# Schematic.net
KiCad netlist of a schematic drawn in Altium Designer
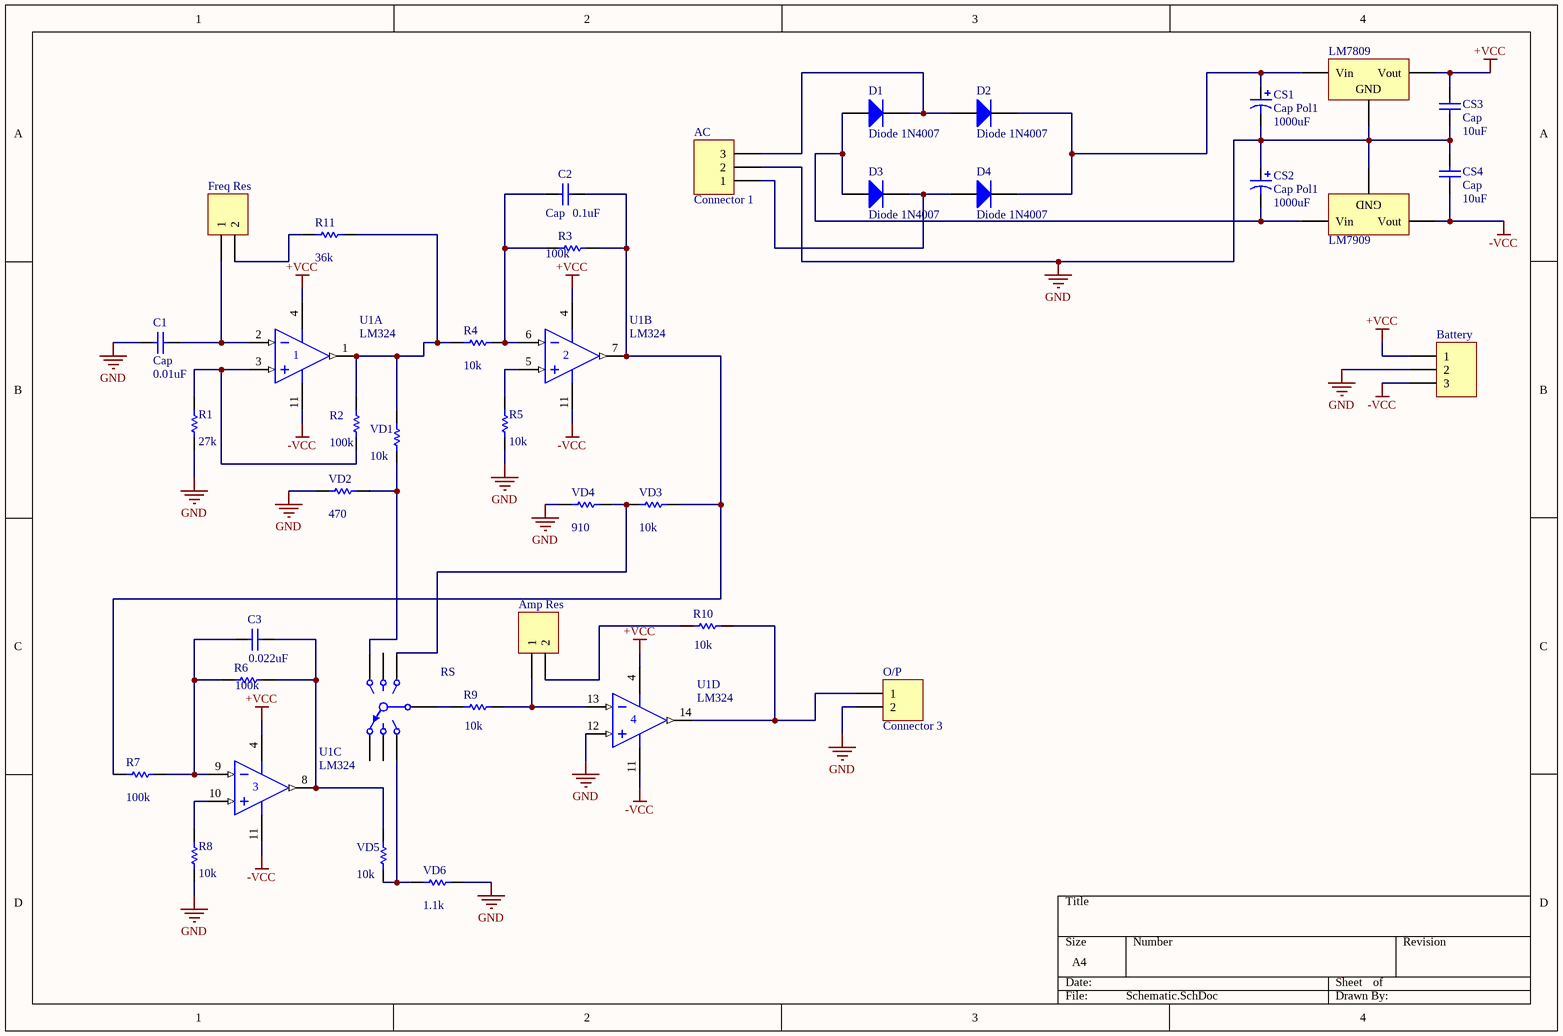
[diagram p0: Schematic.SchDoc]

(export (version "E")
  (design (tool "Eeschema 10.0.6"))
  (components
    (comp (ref "AC")
      (value "Connector 1")
      (footprint "HDR1X3H")
      (description "Header, 3-Pin, Right Angle")
      (fields (field (name "PUBLISHER") "Altium Limited"))
      (libsource (lib "") (part "Header 3H_1"))
    )
    (comp (ref "Amp Res")
      (value "~")
      (footprint "HDR1X2")
      (description "Header, 2-Pin")
      (fields (field (name "PUBLISHER") "Altium Limited"))
      (libsource (lib "Miscellaneous Connectors") (part "Header 2"))
    )
    (comp (ref "Battery")
      (value "~")
      (footprint "HDR1X3H")
      (description "Header, 3-Pin, Right Angle")
      (fields (field (name "PUBLISHER") "Altium Limited"))
      (libsource (lib "Miscellaneous Connectors") (part "Header 3H"))
    )
    (comp (ref "C1")
      (value "Cap")
      (footprint "RAD-0.1")
      (description "Capacitor")
      (fields (field (name "ALTIUM_VALUE") "0.01uF") (field (name "PUBLISHER") "Altium Limited"))
      (libsource (lib "Miscellaneous Devices") (part "Cap"))
    )
    (comp (ref "C2")
      (value "Cap")
      (footprint "RAD-0.1")
      (description "Capacitor")
      (fields (field (name "ALTIUM_VALUE") "0.1uF") (field (name "PUBLISHER") "Altium Limited"))
      (libsource (lib "Miscellaneous Devices") (part "Cap"))
    )
    (comp (ref "C3")
      (value "0.022uF")
      (footprint "RAD-0.1")
      (description "Capacitor")
      (fields (field (name "PUBLISHER") "Altium Limited"))
      (libsource (lib "Miscellaneous Devices") (part "Cap"))
    )
    (comp (ref "CS1")
      (value "Cap Pol1")
      (footprint "RB5-10.5")
      (description "Polarized Capacitor (Radial)")
      (fields (field (name "ALTIUM_VALUE") "1000uF") (field (name "PUBLISHER") "Altium Limited"))
      (libsource (lib "Miscellaneous Devices") (part "Cap Pol1"))
    )
    (comp (ref "CS2")
      (value "Cap Pol1")
      (footprint "RB5-10.5")
      (description "Polarized Capacitor (Radial)")
      (fields (field (name "ALTIUM_VALUE") "1000uF") (field (name "PUBLISHER") "Altium Limited"))
      (libsource (lib "Miscellaneous Devices") (part "Cap Pol1"))
    )
    (comp (ref "CS3")
      (value "Cap")
      (footprint "RAD-0.1")
      (description "Capacitor")
      (fields (field (name "ALTIUM_VALUE") "10uF") (field (name "PUBLISHER") "Altium Limited"))
      (libsource (lib "Miscellaneous Devices") (part "Cap"))
    )
    (comp (ref "CS4")
      (value "Cap")
      (footprint "RAD-0.1")
      (description "Capacitor")
      (fields (field (name "ALTIUM_VALUE") "10uF") (field (name "PUBLISHER") "Altium Limited"))
      (libsource (lib "Miscellaneous Devices") (part "Cap"))
    )
    (comp (ref "D1")
      (value "Diode 1N4007")
      (footprint "DO-41")
      (description "1 Amp General Purpose Rectifier")
      (fields (field (name "PUBLISHER") "Altium Limited"))
      (libsource (lib "Miscellaneous Devices") (part "Diode 1N4007"))
    )
    (comp (ref "D2")
      (value "Diode 1N4007")
      (footprint "DO-41")
      (description "1 Amp General Purpose Rectifier")
      (fields (field (name "PUBLISHER") "Altium Limited"))
      (libsource (lib "Miscellaneous Devices") (part "Diode 1N4007"))
    )
    (comp (ref "D3")
      (value "Diode 1N4007")
      (footprint "DO-41")
      (description "1 Amp General Purpose Rectifier")
      (fields (field (name "PUBLISHER") "Altium Limited"))
      (libsource (lib "Miscellaneous Devices") (part "Diode 1N4007"))
    )
    (comp (ref "D4")
      (value "Diode 1N4007")
      (footprint "DO-41")
      (description "1 Amp General Purpose Rectifier")
      (fields (field (name "PUBLISHER") "Altium Limited"))
      (libsource (lib "Miscellaneous Devices") (part "Diode 1N4007"))
    )
    (comp (ref "Freq Res")
      (value "~")
      (footprint "HDR1X2")
      (description "Header, 2-Pin")
      (fields (field (name "PUBLISHER") "Altium Limited"))
      (libsource (lib "Miscellaneous Connectors") (part "Header 2"))
    )
    (comp (ref "LM7809")
      (value "~")
      (footprint "TO-262-AA")
      (description "Voltage Regulator")
      (fields (field (name "PUBLISHER") "Altium Limited"))
      (libsource (lib "") (part "Volt Reg_1"))
    )
    (comp (ref "LM7909")
      (value "~")
      (footprint "TO-262-AA")
      (description "Voltage Regulator")
      (fields (field (name "PUBLISHER") "Altium Limited"))
      (libsource (lib "Miscellaneous Devices") (part "Volt Reg"))
    )
    (comp (ref "O/P")
      (value "Connector 3")
      (footprint "HDR1X2")
      (description "Header, 2-Pin")
      (fields (field (name "PUBLISHER") "Altium Limited"))
      (libsource (lib "") (part "Header 2_1"))
    )
    (comp (ref "R1")
      (value "27k")
      (footprint "AXIAL-0.4")
      (description "Resistor")
      (fields (field (name "PUBLISHER") "Altium Limited"))
      (libsource (lib "Miscellaneous Devices") (part "Res1"))
    )
    (comp (ref "R2")
      (value "100k")
      (footprint "AXIAL-0.4")
      (description "Resistor")
      (fields (field (name "PUBLISHER") "Altium Limited"))
      (libsource (lib "Miscellaneous Devices") (part "Res1"))
    )
    (comp (ref "R3")
      (value "100k")
      (footprint "AXIAL-0.4")
      (description "Resistor")
      (fields (field (name "PUBLISHER") "Altium Limited"))
      (libsource (lib "Miscellaneous Devices") (part "Res1"))
    )
    (comp (ref "R4")
      (value "10k")
      (footprint "AXIAL-0.4")
      (description "Resistor")
      (fields (field (name "PUBLISHER") "Altium Limited"))
      (libsource (lib "Miscellaneous Devices") (part "Res1"))
    )
    (comp (ref "R5")
      (value "10k")
      (footprint "AXIAL-0.4")
      (description "Resistor")
      (fields (field (name "PUBLISHER") "Altium Limited"))
      (libsource (lib "Miscellaneous Devices") (part "Res1"))
    )
    (comp (ref "R6")
      (value "100k")
      (footprint "AXIAL-0.4")
      (description "Resistor")
      (fields (field (name "PUBLISHER") "Altium Limited"))
      (libsource (lib "Miscellaneous Devices") (part "Res1"))
    )
    (comp (ref "R7")
      (value "100k")
      (footprint "AXIAL-0.4")
      (description "Resistor")
      (fields (field (name "PUBLISHER") "Altium Limited"))
      (libsource (lib "Miscellaneous Devices") (part "Res1"))
    )
    (comp (ref "R8")
      (value "10k")
      (footprint "AXIAL-0.4")
      (description "Resistor")
      (fields (field (name "PUBLISHER") "Altium Limited"))
      (libsource (lib "Miscellaneous Devices") (part "Res1"))
    )
    (comp (ref "R9")
      (value "10k")
      (footprint "AXIAL-0.4")
      (description "Resistor")
      (fields (field (name "PUBLISHER") "Altium Limited"))
      (libsource (lib "Miscellaneous Devices") (part "Res1"))
    )
    (comp (ref "R10")
      (value "10k")
      (footprint "AXIAL-0.4")
      (description "Resistor")
      (fields (field (name "PUBLISHER") "Altium Limited"))
      (libsource (lib "Miscellaneous Devices") (part "Res1"))
    )
    (comp (ref "R11")
      (value "36k")
      (footprint "AXIAL-0.4")
      (description "Resistor")
      (fields (field (name "PUBLISHER") "Altium Limited"))
      (libsource (lib "Miscellaneous Devices") (part "Res1"))
    )
    (comp (ref "RS")
      (value "~")
      (footprint "SW-7")
      (description "6 Way Switch")
      (fields (field (name "PUBLISHER") "Altium Limited"))
      (libsource (lib "Miscellaneous Devices") (part "SW-6WAY"))
    )
    (comp (ref "U1")
      (value "LM324")
      (footprint "646-06")
      (description "Single-Supply 3 to 44 V Operational Amplifier")
      (fields (field (name "PUBLISHER") "Altium Limited"))
      (libsource (lib "ON Semi Operational Amplifier") (part "MC34074VP"))
    )
    (comp (ref "VD1")
      (value "10k")
      (footprint "AXIAL-0.4")
      (description "Resistor")
      (fields (field (name "PUBLISHER") "Altium Limited"))
      (libsource (lib "Miscellaneous Devices") (part "Res1"))
    )
    (comp (ref "VD2")
      (value "470")
      (footprint "AXIAL-0.4")
      (description "Resistor")
      (fields (field (name "PUBLISHER") "Altium Limited"))
      (libsource (lib "Miscellaneous Devices") (part "Res1"))
    )
    (comp (ref "VD3")
      (value "10k")
      (footprint "AXIAL-0.4")
      (description "Resistor")
      (fields (field (name "PUBLISHER") "Altium Limited"))
      (libsource (lib "Miscellaneous Devices") (part "Res1"))
    )
    (comp (ref "VD4")
      (value "910")
      (footprint "AXIAL-0.4")
      (description "Resistor")
      (fields (field (name "PUBLISHER") "Altium Limited"))
      (libsource (lib "Miscellaneous Devices") (part "Res1"))
    )
    (comp (ref "VD5")
      (value "10k")
      (footprint "AXIAL-0.4")
      (description "Resistor")
      (fields (field (name "PUBLISHER") "Altium Limited"))
      (libsource (lib "Miscellaneous Devices") (part "Res1"))
    )
    (comp (ref "VD6")
      (value "1.1k")
      (footprint "AXIAL-0.4")
      (description "Resistor")
      (fields (field (name "PUBLISHER") "Altium Limited"))
      (libsource (lib "Miscellaneous Devices") (part "Res1"))
    )
  )
  (nets
    (net (code "1") (name "+VCC") (class "Default")
      (node (ref "Battery") (pin "1") (pinfunction "1_1") (pintype "passive"))
      (node (ref "CS3") (pin "2") (pinfunction "2_2") (pintype "passive"))
      (node (ref "LM7809") (pin "3") (pinfunction "Vout_3") (pintype "passive"))
      (node (ref "U1") (pin "4") (pinfunction "V+_4") (pintype "power_in"))
    )
    (net (code "2") (name "-VCC") (class "Default")
      (node (ref "Battery") (pin "3") (pinfunction "3_3") (pintype "passive"))
      (node (ref "CS4") (pin "1") (pinfunction "1_1") (pintype "passive"))
      (node (ref "LM7909") (pin "3") (pinfunction "Vout_3") (pintype "passive"))
      (node (ref "U1") (pin "11") (pinfunction "V-_11") (pintype "power_in"))
    )
    (net (code "3") (name "GND") (class "Default")
      (node (ref "AC") (pin "2") (pinfunction "2_2") (pintype "passive"))
      (node (ref "Battery") (pin "2") (pinfunction "2_2") (pintype "passive"))
      (node (ref "C1") (pin "2") (pinfunction "2_2") (pintype "passive"))
      (node (ref "CS1") (pin "2") (pinfunction "2_2") (pintype "passive"))
      (node (ref "CS2") (pin "1") (pinfunction "1_1") (pintype "passive"))
      (node (ref "CS3") (pin "1") (pinfunction "1_1") (pintype "passive"))
      (node (ref "CS4") (pin "2") (pinfunction "2_2") (pintype "passive"))
      (node (ref "LM7809") (pin "2") (pinfunction "GND_2") (pintype "passive"))
      (node (ref "LM7909") (pin "2") (pinfunction "GND_2") (pintype "passive"))
      (node (ref "O/P") (pin "2") (pinfunction "2_2") (pintype "passive"))
      (node (ref "R1") (pin "2") (pinfunction "2_2") (pintype "passive"))
      (node (ref "R5") (pin "1") (pinfunction "1_1") (pintype "passive"))
      (node (ref "R8") (pin "2") (pinfunction "2_2") (pintype "passive"))
      (node (ref "U1") (pin "12") (pinfunction "IN+_12") (pintype "input"))
      (node (ref "VD2") (pin "1") (pinfunction "1_1") (pintype "passive"))
      (node (ref "VD4") (pin "1") (pinfunction "1_1") (pintype "passive"))
      (node (ref "VD6") (pin "2") (pinfunction "2_2") (pintype "passive"))
    )
    (net (code "4") (name "Net-(Amp Res-Pad2)") (class "Default")
      (node (ref "Amp Res") (pin "2") (pinfunction "2_2") (pintype "passive"))
      (node (ref "R10") (pin "1") (pinfunction "1_1") (pintype "passive"))
    )
    (net (code "5") (name "Net-(D1-A)") (class "Default")
      (node (ref "CS2") (pin "2") (pinfunction "2_2") (pintype "passive"))
      (node (ref "D1") (pin "1") (pinfunction "A_1") (pintype "passive"))
      (node (ref "D3") (pin "1") (pinfunction "A_1") (pintype "passive"))
      (node (ref "LM7909") (pin "1") (pinfunction "Vin_1") (pintype "passive"))
    )
    (net (code "6") (name "Net-(D1-K)") (class "Default")
      (node (ref "AC") (pin "3") (pinfunction "3_3") (pintype "passive"))
      (node (ref "D1") (pin "2") (pinfunction "K_2") (pintype "passive"))
      (node (ref "D2") (pin "1") (pinfunction "A_1") (pintype "passive"))
    )
    (net (code "7") (name "Net-(D2-K)") (class "Default")
      (node (ref "CS1") (pin "1") (pinfunction "1_1") (pintype "passive"))
      (node (ref "D2") (pin "2") (pinfunction "K_2") (pintype "passive"))
      (node (ref "D4") (pin "2") (pinfunction "K_2") (pintype "passive"))
      (node (ref "LM7809") (pin "1") (pinfunction "Vin_1") (pintype "passive"))
    )
    (net (code "8") (name "Net-(D3-K)") (class "Default")
      (node (ref "AC") (pin "1") (pinfunction "1_1") (pintype "passive"))
      (node (ref "D3") (pin "2") (pinfunction "K_2") (pintype "passive"))
      (node (ref "D4") (pin "1") (pinfunction "A_1") (pintype "passive"))
    )
    (net (code "9") (name "Net-(Freq Res-Pad2)") (class "Default")
      (node (ref "Freq Res") (pin "2") (pinfunction "2_2") (pintype "passive"))
      (node (ref "R11") (pin "1") (pinfunction "1_1") (pintype "passive"))
    )
    (net (code "10") (name "Net-(R9-Pad1)") (class "Default")
      (node (ref "R9") (pin "1") (pinfunction "1_1") (pintype "passive"))
      (node (ref "RS") (pin "7") (pinfunction "7_7") (pintype "passive"))
    )
    (net (code "11") (name "Net-(RS-Pad1)") (class "Default")
      (node (ref "RS") (pin "1") (pinfunction "1_1") (pintype "passive"))
      (node (ref "VD3") (pin "1") (pinfunction "1_1") (pintype "passive"))
      (node (ref "VD4") (pin "2") (pinfunction "2_2") (pintype "passive"))
    )
    (net (code "12") (name "Net-(RS-Pad3)") (class "Default")
      (node (ref "RS") (pin "3") (pinfunction "3_3") (pintype "passive"))
      (node (ref "VD1") (pin "2") (pinfunction "2_2") (pintype "passive"))
      (node (ref "VD2") (pin "2") (pinfunction "2_2") (pintype "passive"))
    )
    (net (code "13") (name "Net-(RS-Pad4)") (class "Default")
      (node (ref "RS") (pin "4") (pinfunction "4_4") (pintype "passive"))
      (node (ref "VD5") (pin "2") (pinfunction "2_2") (pintype "passive"))
      (node (ref "VD6") (pin "1") (pinfunction "1_1") (pintype "passive"))
    )
    (net (code "14") (name "Net-(U1A-IN+)") (class "Default")
      (node (ref "R1") (pin "1") (pinfunction "1_1") (pintype "passive"))
      (node (ref "R2") (pin "2") (pinfunction "2_2") (pintype "passive"))
      (node (ref "U1") (pin "3") (pinfunction "IN+_3") (pintype "input"))
    )
    (net (code "15") (name "Net-(U1A-IN-)") (class "Default")
      (node (ref "C1") (pin "1") (pinfunction "1_1") (pintype "passive"))
      (node (ref "Freq Res") (pin "1") (pinfunction "1_1") (pintype "passive"))
      (node (ref "U1") (pin "2") (pinfunction "IN-_2") (pintype "input"))
    )
    (net (code "16") (name "Net-(U1A-OUT)") (class "Default")
      (node (ref "R11") (pin "2") (pinfunction "2_2") (pintype "passive"))
      (node (ref "R2") (pin "1") (pinfunction "1_1") (pintype "passive"))
      (node (ref "R4") (pin "2") (pinfunction "2_2") (pintype "passive"))
      (node (ref "U1") (pin "1") (pinfunction "OUT_1") (pintype "output"))
      (node (ref "VD1") (pin "1") (pinfunction "1_1") (pintype "passive"))
    )
    (net (code "17") (name "Net-(U1B-IN+)") (class "Default")
      (node (ref "R5") (pin "2") (pinfunction "2_2") (pintype "passive"))
      (node (ref "U1") (pin "5") (pinfunction "IN+_5") (pintype "input"))
    )
    (net (code "18") (name "Net-(U1B-IN-)") (class "Default")
      (node (ref "C2") (pin "2") (pinfunction "2_2") (pintype "passive"))
      (node (ref "R3") (pin "1") (pinfunction "1_1") (pintype "passive"))
      (node (ref "R4") (pin "1") (pinfunction "1_1") (pintype "passive"))
      (node (ref "U1") (pin "6") (pinfunction "IN-_6") (pintype "input"))
    )
    (net (code "19") (name "Net-(U1B-OUT)") (class "Default")
      (node (ref "C2") (pin "1") (pinfunction "1_1") (pintype "passive"))
      (node (ref "R3") (pin "2") (pinfunction "2_2") (pintype "passive"))
      (node (ref "R7") (pin "1") (pinfunction "1_1") (pintype "passive"))
      (node (ref "U1") (pin "7") (pinfunction "OUT_7") (pintype "output"))
      (node (ref "VD3") (pin "2") (pinfunction "2_2") (pintype "passive"))
    )
    (net (code "20") (name "Net-(U1C-IN+)") (class "Default")
      (node (ref "R8") (pin "1") (pinfunction "1_1") (pintype "passive"))
      (node (ref "U1") (pin "10") (pinfunction "IN+_10") (pintype "input"))
    )
    (net (code "21") (name "Net-(U1C-IN-)") (class "Default")
      (node (ref "C3") (pin "2") (pinfunction "2_2") (pintype "passive"))
      (node (ref "R6") (pin "1") (pinfunction "1_1") (pintype "passive"))
      (node (ref "R7") (pin "2") (pinfunction "2_2") (pintype "passive"))
      (node (ref "U1") (pin "9") (pinfunction "IN-_9") (pintype "input"))
    )
    (net (code "22") (name "Net-(U1C-OUT)") (class "Default")
      (node (ref "C3") (pin "1") (pinfunction "1_1") (pintype "passive"))
      (node (ref "R6") (pin "2") (pinfunction "2_2") (pintype "passive"))
      (node (ref "U1") (pin "8") (pinfunction "OUT_8") (pintype "output"))
      (node (ref "VD5") (pin "1") (pinfunction "1_1") (pintype "passive"))
    )
    (net (code "23") (name "Net-(U1D-IN-)") (class "Default")
      (node (ref "Amp Res") (pin "1") (pinfunction "1_1") (pintype "passive"))
      (node (ref "R9") (pin "2") (pinfunction "2_2") (pintype "passive"))
      (node (ref "U1") (pin "13") (pinfunction "IN-_13") (pintype "input"))
    )
    (net (code "24") (name "Net-(U1D-OUT)") (class "Default")
      (node (ref "O/P") (pin "1") (pinfunction "1_1") (pintype "passive"))
      (node (ref "R10") (pin "2") (pinfunction "2_2") (pintype "passive"))
      (node (ref "U1") (pin "14") (pinfunction "OUT_14") (pintype "output"))
    )
    (net (code "25") (name "unconnected-(RS-Pad2)") (class "Default")
      (node (ref "RS") (pin "2") (pinfunction "2_2") (pintype "passive"))
    )
    (net (code "26") (name "unconnected-(RS-Pad5)") (class "Default")
      (node (ref "RS") (pin "5") (pinfunction "5_5") (pintype "passive"))
    )
    (net (code "27") (name "unconnected-(RS-Pad6)") (class "Default")
      (node (ref "RS") (pin "6") (pinfunction "6_6") (pintype "passive"))
    )
  )
)
